# Rotary_Encoder_Breakout.net
KiCad netlist of a schematic drawn in EAGLE
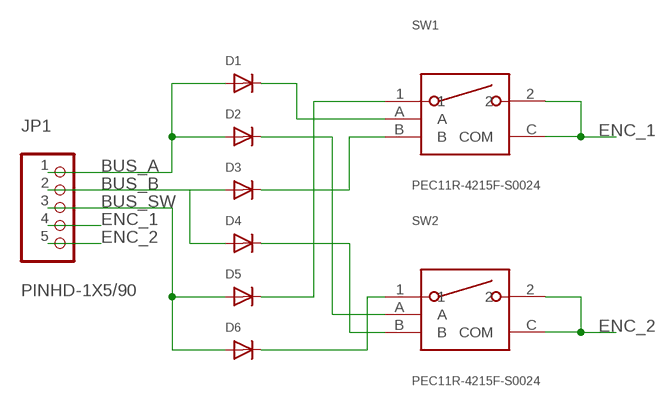
[diagram p0: schematic, sheet 1]

(export (version "E")
  (design (tool "Eeschema 10.0.6"))
  (components
    (comp (ref "D1")
      (value "DIODESOD-123")
      (footprint "eagle-import:SOD-123")
      (libsource (lib "eagle-import") (part "DIODESOD-123"))
    )
    (comp (ref "D2")
      (value "DIODESOD-123")
      (footprint "eagle-import:SOD-123")
      (libsource (lib "eagle-import") (part "DIODESOD-123"))
    )
    (comp (ref "D3")
      (value "DIODESOD-123")
      (footprint "eagle-import:SOD-123")
      (libsource (lib "eagle-import") (part "DIODESOD-123"))
    )
    (comp (ref "D4")
      (value "DIODESOD-123")
      (footprint "eagle-import:SOD-123")
      (libsource (lib "eagle-import") (part "DIODESOD-123"))
    )
    (comp (ref "D5")
      (value "DIODESOD-123")
      (footprint "eagle-import:SOD-123")
      (libsource (lib "eagle-import") (part "DIODESOD-123"))
    )
    (comp (ref "D6")
      (value "DIODESOD-123")
      (footprint "eagle-import:SOD-123")
      (libsource (lib "eagle-import") (part "DIODESOD-123"))
    )
    (comp (ref "JP1")
      (value "PINHD-1X5/90")
      (footprint "eagle-import:1X05_90")
      (libsource (lib "eagle-import") (part "PINHD-1X5/90"))
    )
    (comp (ref "SW1")
      (value "PEC11R-4215F-S0024")
      (footprint "eagle-import:PEC11R-4215F-S0024")
      (fields
        (field (name "DIGIKEY_PART_NUMBER") "PEC11R-4215F-S0024-ND")
        (field (name "MANUFACTURER") "Bourns Inc.")
        (field (name "CREATED_BY") "PCBLayout.com")
      )
      (libsource (lib "eagle-import") (part "PEC11R-4215F-S0024"))
    )
    (comp (ref "SW2")
      (value "PEC11R-4215F-S0024")
      (footprint "eagle-import:PEC11R-4215F-S0024")
      (fields
        (field (name "DIGIKEY_PART_NUMBER") "PEC11R-4215F-S0024-ND")
        (field (name "MANUFACTURER") "Bourns Inc.")
        (field (name "CREATED_BY") "PCBLayout.com")
      )
      (libsource (lib "eagle-import") (part "PEC11R-4215F-S0024"))
    )
  )
  (nets
    (net (code "1") (name "/BUS_A") (class "Default")
      (node (ref "D1") (pin "A") (pinfunction "A_A") (pintype "passive"))
      (node (ref "D2") (pin "A") (pinfunction "A_A") (pintype "passive"))
      (node (ref "JP1") (pin "1") (pinfunction "1_1") (pintype "passive"))
    )
    (net (code "2") (name "/BUS_B") (class "Default")
      (node (ref "D3") (pin "A") (pinfunction "A_A") (pintype "passive"))
      (node (ref "D4") (pin "A") (pinfunction "A_A") (pintype "passive"))
      (node (ref "JP1") (pin "2") (pinfunction "2_2") (pintype "passive"))
    )
    (net (code "3") (name "/BUS_SW") (class "Default")
      (node (ref "D5") (pin "A") (pinfunction "A_A") (pintype "passive"))
      (node (ref "D6") (pin "A") (pinfunction "A_A") (pintype "passive"))
      (node (ref "JP1") (pin "3") (pinfunction "3_3") (pintype "passive"))
    )
    (net (code "4") (name "/ENC_1") (class "Default")
      (node (ref "JP1") (pin "4") (pinfunction "4_4") (pintype "passive"))
      (node (ref "SW1") (pin "2") (pinfunction "2_2") (pintype "passive"))
      (node (ref "SW1") (pin "C") (pinfunction "COM_C") (pintype "passive"))
    )
    (net (code "5") (name "/ENC_2") (class "Default")
      (node (ref "JP1") (pin "5") (pinfunction "5_5") (pintype "passive"))
      (node (ref "SW2") (pin "2") (pinfunction "2_2") (pintype "passive"))
      (node (ref "SW2") (pin "C") (pinfunction "COM_C") (pintype "passive"))
    )
    (net (code "6") (name "Net-(D1-PadC)") (class "Default")
      (node (ref "D1") (pin "C") (pinfunction "C_C") (pintype "passive"))
      (node (ref "SW1") (pin "A") (pinfunction "A_A") (pintype "passive"))
    )
    (net (code "7") (name "Net-(D2-PadC)") (class "Default")
      (node (ref "D2") (pin "C") (pinfunction "C_C") (pintype "passive"))
      (node (ref "SW2") (pin "A") (pinfunction "A_A") (pintype "passive"))
    )
    (net (code "8") (name "Net-(D3-PadC)") (class "Default")
      (node (ref "D3") (pin "C") (pinfunction "C_C") (pintype "passive"))
      (node (ref "SW1") (pin "B") (pinfunction "B_B") (pintype "passive"))
    )
    (net (code "9") (name "Net-(D4-PadC)") (class "Default")
      (node (ref "D4") (pin "C") (pinfunction "C_C") (pintype "passive"))
      (node (ref "SW2") (pin "B") (pinfunction "B_B") (pintype "passive"))
    )
    (net (code "10") (name "Net-(D5-PadC)") (class "Default")
      (node (ref "D5") (pin "C") (pinfunction "C_C") (pintype "passive"))
      (node (ref "SW1") (pin "1") (pinfunction "1_1") (pintype "passive"))
    )
    (net (code "11") (name "Net-(D6-PadC)") (class "Default")
      (node (ref "D6") (pin "C") (pinfunction "C_C") (pintype "passive"))
      (node (ref "SW2") (pin "1") (pinfunction "1_1") (pintype "passive"))
    )
  )
)
